# PLCC120_breakout.net
KiCad netlist of a schematic drawn in EAGLE
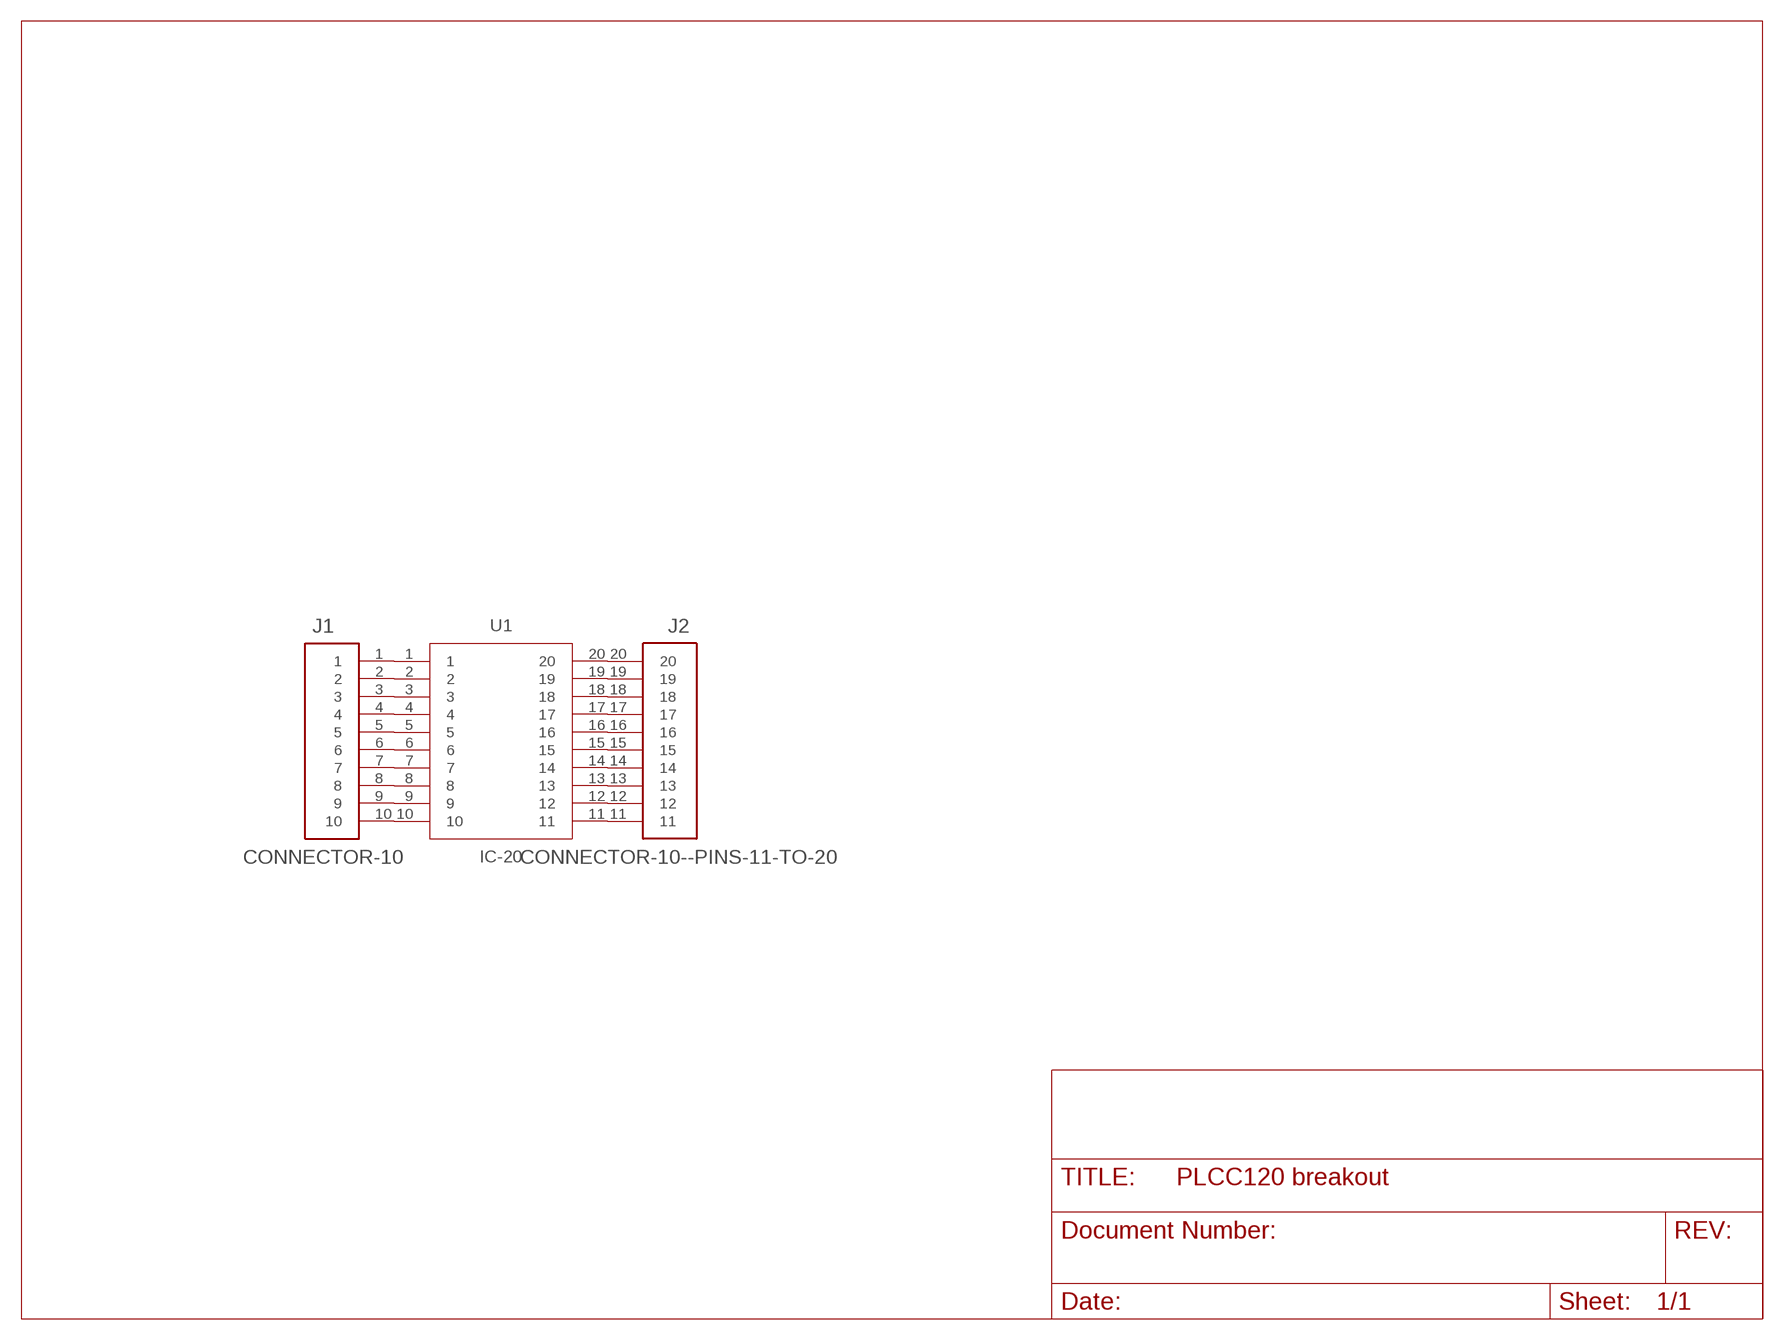
[diagram p0: schematic, sheet 1]

(export (version "E")
  (design (tool "Eeschema 10.0.6"))
  (components
    (comp (ref "J1")
      (value "CONNECTOR-10")
      (footprint "eagle-import:ESQ-110-XX-XX-S")
      (libsource (lib "eagle-import") (part "CONNECTOR-10"))
    )
    (comp (ref "J2")
      (value "CONNECTOR-10--PINS-11-TO-20")
      (footprint "eagle-import:ESQ-110-XX-XX-S--ROUND-PIN-1")
      (libsource (lib "eagle-import") (part "CONNECTOR-10--PINS-11-TO-20"))
    )
    (comp (ref "U1")
      (value "IC-20")
      (footprint "eagle-import:PLCC127P990X990X457-20N")
      (libsource (lib "eagle-import") (part "IC-20"))
    )
  )
  (nets
    (net (code "1") (name "Net-(J1-Pad1)") (class "Default")
      (node (ref "J1") (pin "1") (pinfunction "1_1") (pintype "bidirectional"))
      (node (ref "U1") (pin "1") (pinfunction "1_1") (pintype "bidirectional"))
    )
    (net (code "2") (name "Net-(J1-Pad2)") (class "Default")
      (node (ref "J1") (pin "2") (pinfunction "2_2") (pintype "bidirectional"))
      (node (ref "U1") (pin "2") (pinfunction "2_2") (pintype "bidirectional"))
    )
    (net (code "3") (name "Net-(J1-Pad3)") (class "Default")
      (node (ref "J1") (pin "3") (pinfunction "3_3") (pintype "bidirectional"))
      (node (ref "U1") (pin "3") (pinfunction "3_3") (pintype "bidirectional"))
    )
    (net (code "4") (name "Net-(J1-Pad4)") (class "Default")
      (node (ref "J1") (pin "4") (pinfunction "4_4") (pintype "bidirectional"))
      (node (ref "U1") (pin "4") (pinfunction "4_4") (pintype "bidirectional"))
    )
    (net (code "5") (name "Net-(J1-Pad5)") (class "Default")
      (node (ref "J1") (pin "5") (pinfunction "5_5") (pintype "bidirectional"))
      (node (ref "U1") (pin "5") (pinfunction "5_5") (pintype "bidirectional"))
    )
    (net (code "6") (name "Net-(J1-Pad6)") (class "Default")
      (node (ref "J1") (pin "6") (pinfunction "6_6") (pintype "bidirectional"))
      (node (ref "U1") (pin "6") (pinfunction "6_6") (pintype "bidirectional"))
    )
    (net (code "7") (name "Net-(J1-Pad7)") (class "Default")
      (node (ref "J1") (pin "7") (pinfunction "7_7") (pintype "bidirectional"))
      (node (ref "U1") (pin "7") (pinfunction "7_7") (pintype "bidirectional"))
    )
    (net (code "8") (name "Net-(J1-Pad8)") (class "Default")
      (node (ref "J1") (pin "8") (pinfunction "8_8") (pintype "bidirectional"))
      (node (ref "U1") (pin "8") (pinfunction "8_8") (pintype "bidirectional"))
    )
    (net (code "9") (name "Net-(J1-Pad9)") (class "Default")
      (node (ref "J1") (pin "9") (pinfunction "9_9") (pintype "bidirectional"))
      (node (ref "U1") (pin "9") (pinfunction "9_9") (pintype "bidirectional"))
    )
    (net (code "10") (name "Net-(J1-Pad10)") (class "Default")
      (node (ref "J1") (pin "10") (pinfunction "10_10") (pintype "bidirectional"))
      (node (ref "U1") (pin "10") (pinfunction "10_10") (pintype "bidirectional"))
    )
    (net (code "11") (name "Net-(J2-Pad11)") (class "Default")
      (node (ref "J2") (pin "11") (pinfunction "11_11") (pintype "bidirectional"))
      (node (ref "U1") (pin "11") (pinfunction "11_11") (pintype "bidirectional"))
    )
    (net (code "12") (name "Net-(J2-Pad12)") (class "Default")
      (node (ref "J2") (pin "12") (pinfunction "12_12") (pintype "bidirectional"))
      (node (ref "U1") (pin "12") (pinfunction "12_12") (pintype "bidirectional"))
    )
    (net (code "13") (name "Net-(J2-Pad13)") (class "Default")
      (node (ref "J2") (pin "13") (pinfunction "13_13") (pintype "bidirectional"))
      (node (ref "U1") (pin "13") (pinfunction "13_13") (pintype "bidirectional"))
    )
    (net (code "14") (name "Net-(J2-Pad14)") (class "Default")
      (node (ref "J2") (pin "14") (pinfunction "14_14") (pintype "bidirectional"))
      (node (ref "U1") (pin "14") (pinfunction "14_14") (pintype "bidirectional"))
    )
    (net (code "15") (name "Net-(J2-Pad15)") (class "Default")
      (node (ref "J2") (pin "15") (pinfunction "15_15") (pintype "bidirectional"))
      (node (ref "U1") (pin "15") (pinfunction "15_15") (pintype "bidirectional"))
    )
    (net (code "16") (name "Net-(J2-Pad16)") (class "Default")
      (node (ref "J2") (pin "16") (pinfunction "16_16") (pintype "bidirectional"))
      (node (ref "U1") (pin "16") (pinfunction "16_16") (pintype "bidirectional"))
    )
    (net (code "17") (name "Net-(J2-Pad17)") (class "Default")
      (node (ref "J2") (pin "17") (pinfunction "17_17") (pintype "bidirectional"))
      (node (ref "U1") (pin "17") (pinfunction "17_17") (pintype "bidirectional"))
    )
    (net (code "18") (name "Net-(J2-Pad18)") (class "Default")
      (node (ref "J2") (pin "18") (pinfunction "18_18") (pintype "bidirectional"))
      (node (ref "U1") (pin "18") (pinfunction "18_18") (pintype "bidirectional"))
    )
    (net (code "19") (name "Net-(J2-Pad19)") (class "Default")
      (node (ref "J2") (pin "19") (pinfunction "19_19") (pintype "bidirectional"))
      (node (ref "U1") (pin "19") (pinfunction "19_19") (pintype "bidirectional"))
    )
    (net (code "20") (name "Net-(J2-Pad20)") (class "Default")
      (node (ref "J2") (pin "20") (pinfunction "20_20") (pintype "bidirectional"))
      (node (ref "U1") (pin "20") (pinfunction "20_20") (pintype "bidirectional"))
    )
  )
)
